# PIC.net
KiCad netlist of a schematic drawn in Altium Designer
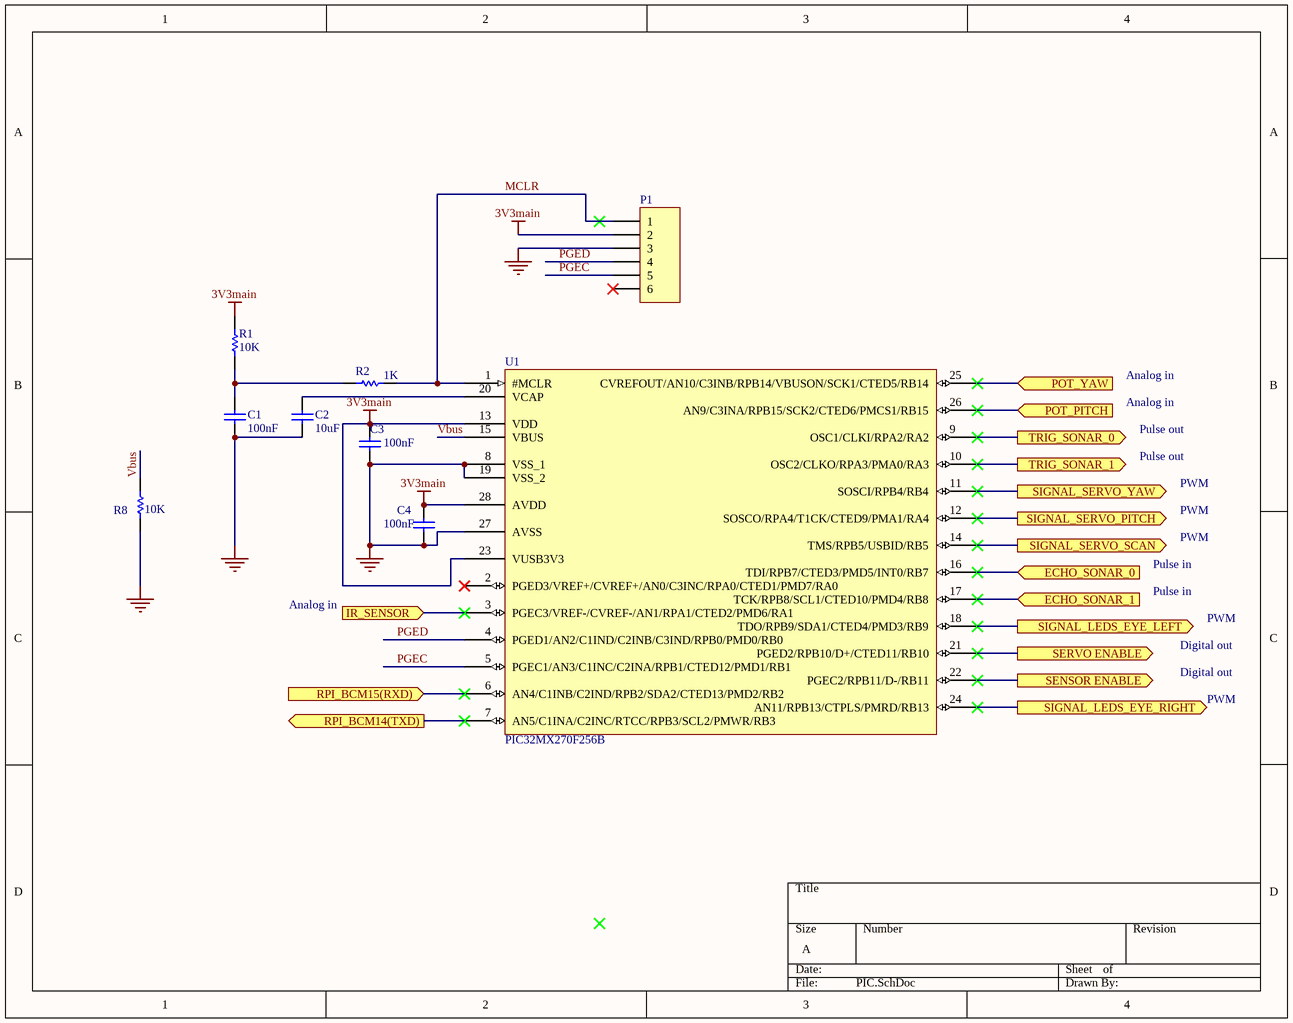
[diagram p0: PIC.SchDoc]

(export (version "E")
  (design (tool "Eeschema 10.0.6"))
  (components
    (comp (ref "C1")
      (value "100nF")
      (footprint "1608 / 0603")
      (description "Capacitor")
      (fields (field (name "PUBLISHER") "Altium Limited"))
      (libsource (lib "Miscellaneous Devices") (part "Cap"))
    )
    (comp (ref "C2")
      (value "10uF")
      (footprint "1608 / 0603")
      (description "Capacitor")
      (fields (field (name "PUBLISHER") "Altium Limited"))
      (libsource (lib "Miscellaneous Devices") (part "Cap"))
    )
    (comp (ref "C3")
      (value "100nF")
      (footprint "1608 / 0603")
      (description "Capacitor")
      (fields (field (name "PUBLISHER") "Altium Limited"))
      (libsource (lib "Miscellaneous Devices") (part "Cap"))
    )
    (comp (ref "C4")
      (value "100nF")
      (footprint "1608 / 0603")
      (description "Capacitor")
      (fields (field (name "PUBLISHER") "Altium Limited"))
      (libsource (lib "Miscellaneous Devices") (part "Cap"))
    )
    (comp (ref "P1")
      (value "RJ11 Debug")
      (footprint "MarvinPcbLib2:RJ11")
      (description "RJ11 Connector")
      (fields (field (name "PUBLISHER") "Altium Limited"))
      (libsource (lib "Miscellaneous Connectors") (part "Header 6"))
    )
    (comp (ref "R1")
      (value "10K")
      (footprint "1608 / 0603")
      (description "Resistor")
      (fields (field (name "PUBLISHER") "Altium Limited"))
      (libsource (lib "Miscellaneous Devices") (part "Res1"))
    )
    (comp (ref "R2")
      (value "1K")
      (footprint "1608 / 0603")
      (description "Resistor")
      (fields (field (name "PUBLISHER") "Altium Limited"))
      (libsource (lib "Miscellaneous Devices") (part "Res1"))
    )
    (comp (ref "R8")
      (value "10K")
      (footprint "1608 / 0603")
      (description "Resistor")
      (fields (field (name "PUBLISHER") "Altium Limited"))
      (libsource (lib "Miscellaneous Devices") (part "Res1"))
    )
    (comp (ref "U1")
      (value "PIC32MX270F256B")
      (footprint "MarvinPcbLib2:SOIC28")
      (libsource (lib "POC_Marvin") (part "PIC32MX270F256B"))
    )
  )
  (nets
    (net (code "1") (name "/ECHO_SONAR_0") (class "Default")
      (node (ref "U1") (pin "16") (pinfunction "TDI/RPB7/CTED3/PMD5/INT0/RB7_16") (pintype "bidirectional+no_connect"))
    )
    (net (code "2") (name "/ECHO_SONAR_1") (class "Default")
      (node (ref "U1") (pin "17") (pinfunction "TCK/RPB8/SCL1/CTED10/PMD4/RB8_17") (pintype "bidirectional+no_connect"))
    )
    (net (code "3") (name "/IR_SENSOR") (class "Default")
      (node (ref "U1") (pin "3") (pinfunction "PGEC3/VREF-/CVREF-/AN1/RPA1/CTED2/PMD6/RA1_3") (pintype "bidirectional+no_connect"))
    )
    (net (code "4") (name "/MCLR") (class "Default")
      (node (ref "P1") (pin "1") (pinfunction "1_1") (pintype "passive"))
      (node (ref "R2") (pin "2") (pinfunction "2_2") (pintype "passive"))
      (node (ref "U1") (pin "1") (pinfunction "#MCLR_1") (pintype "input"))
    )
    (net (code "5") (name "/PGEC") (class "Default")
      (node (ref "P1") (pin "5") (pinfunction "5_5") (pintype "passive"))
      (node (ref "U1") (pin "5") (pinfunction "PGEC1/AN3/C1INC/C2INA/RPB1/CTED12/PMD1/RB1_5") (pintype "bidirectional"))
    )
    (net (code "6") (name "/PGED") (class "Default")
      (node (ref "P1") (pin "4") (pinfunction "4_4") (pintype "passive"))
      (node (ref "U1") (pin "4") (pinfunction "PGED1/AN2/C1IND/C2INB/C3IND/RPB0/PMD0/RB0_4") (pintype "bidirectional"))
    )
    (net (code "7") (name "/POT_PITCH") (class "Default")
      (node (ref "U1") (pin "26") (pinfunction "AN9/C3INA/RPB15/SCK2/CTED6/PMCS1/RB15_26") (pintype "bidirectional+no_connect"))
    )
    (net (code "8") (name "/POT_YAW") (class "Default")
      (node (ref "U1") (pin "25") (pinfunction "CVREFOUT/AN10/C3INB/RPB14/VBUSON/SCK1/CTED5/RB14_25") (pintype "bidirectional+no_connect"))
    )
    (net (code "9") (name "/RPI_BCM14(TXD)") (class "Default")
      (node (ref "U1") (pin "7") (pinfunction "AN5/C1INA/C2INC/RTCC/RPB3/SCL2/PMWR/RB3_7") (pintype "bidirectional+no_connect"))
    )
    (net (code "10") (name "/RPI_BCM15(RXD)") (class "Default")
      (node (ref "U1") (pin "6") (pinfunction "AN4/C1INB/C2IND/RPB2/SDA2/CTED13/PMD2/RB2_6") (pintype "bidirectional+no_connect"))
    )
    (net (code "11") (name "/SENSOR ENABLE") (class "Default")
      (node (ref "U1") (pin "22") (pinfunction "PGEC2/RPB11/D-/RB11_22") (pintype "bidirectional+no_connect"))
    )
    (net (code "12") (name "/SERVO ENABLE") (class "Default")
      (node (ref "U1") (pin "21") (pinfunction "PGED2/RPB10/D+/CTED11/RB10_21") (pintype "bidirectional+no_connect"))
    )
    (net (code "13") (name "/SIGNAL_LEDS_EYE_LEFT") (class "Default")
      (node (ref "U1") (pin "18") (pinfunction "TDO/RPB9/SDA1/CTED4/PMD3/RB9_18") (pintype "bidirectional+no_connect"))
    )
    (net (code "14") (name "/SIGNAL_LEDS_EYE_RIGHT") (class "Default")
      (node (ref "U1") (pin "24") (pinfunction "AN11/RPB13/CTPLS/PMRD/RB13_24") (pintype "bidirectional+no_connect"))
    )
    (net (code "15") (name "/SIGNAL_SERVO_PITCH") (class "Default")
      (node (ref "U1") (pin "12") (pinfunction "SOSCO/RPA4/T1CK/CTED9/PMA1/RA4_12") (pintype "bidirectional+no_connect"))
    )
    (net (code "16") (name "/SIGNAL_SERVO_SCAN") (class "Default")
      (node (ref "U1") (pin "14") (pinfunction "TMS/RPB5/USBID/RB5_14") (pintype "bidirectional+no_connect"))
    )
    (net (code "17") (name "/SIGNAL_SERVO_YAW") (class "Default")
      (node (ref "U1") (pin "11") (pinfunction "SOSCI/RPB4/RB4_11") (pintype "bidirectional+no_connect"))
    )
    (net (code "18") (name "/TRIG_SONAR_0") (class "Default")
      (node (ref "U1") (pin "9") (pinfunction "OSC1/CLKI/RPA2/RA2_9") (pintype "bidirectional+no_connect"))
    )
    (net (code "19") (name "/TRIG_SONAR_1") (class "Default")
      (node (ref "U1") (pin "10") (pinfunction "OSC2/CLKO/RPA3/PMA0/RA3_10") (pintype "bidirectional+no_connect"))
    )
    (net (code "20") (name "/Vbus") (class "Default")
      (node (ref "R8") (pin "2") (pinfunction "2_2") (pintype "passive"))
      (node (ref "U1") (pin "15") (pinfunction "VBUS_15") (pintype "power_in"))
    )
    (net (code "21") (name "3V3main") (class "Default")
      (node (ref "C3") (pin "2") (pinfunction "2_2") (pintype "passive"))
      (node (ref "C4") (pin "2") (pinfunction "2_2") (pintype "passive"))
      (node (ref "P1") (pin "2") (pinfunction "2_2") (pintype "passive"))
      (node (ref "R1") (pin "2") (pinfunction "2_2") (pintype "passive"))
      (node (ref "U1") (pin "13") (pinfunction "VDD_13") (pintype "power_in"))
      (node (ref "U1") (pin "23") (pinfunction "VUSB3V3_23") (pintype "power_in"))
      (node (ref "U1") (pin "28") (pinfunction "AVDD_28") (pintype "power_in"))
    )
    (net (code "22") (name "GND") (class "Default")
      (node (ref "C1") (pin "1") (pinfunction "1_1") (pintype "passive"))
      (node (ref "C2") (pin "1") (pinfunction "1_1") (pintype "passive"))
      (node (ref "C3") (pin "1") (pinfunction "1_1") (pintype "passive"))
      (node (ref "C4") (pin "1") (pinfunction "1_1") (pintype "passive"))
      (node (ref "P1") (pin "3") (pinfunction "3_3") (pintype "passive"))
      (node (ref "R8") (pin "1") (pinfunction "1_1") (pintype "passive"))
      (node (ref "U1") (pin "19") (pinfunction "VSS_2_19") (pintype "power_in"))
      (node (ref "U1") (pin "27") (pinfunction "AVSS_27") (pintype "power_in"))
      (node (ref "U1") (pin "8") (pinfunction "VSS_1_8") (pintype "power_in"))
    )
    (net (code "23") (name "Net-(C1-Pad2)") (class "Default")
      (node (ref "C1") (pin "2") (pinfunction "2_2") (pintype "passive"))
      (node (ref "R1") (pin "1") (pinfunction "1_1") (pintype "passive"))
      (node (ref "R2") (pin "1") (pinfunction "1_1") (pintype "passive"))
    )
    (net (code "24") (name "Net-(U1-VCAP)") (class "Default")
      (node (ref "C2") (pin "2") (pinfunction "2_2") (pintype "passive"))
      (node (ref "U1") (pin "20") (pinfunction "VCAP_20") (pintype "power_in"))
    )
    (net (code "25") (name "unconnected-(P1-Pad6)") (class "Default")
      (node (ref "P1") (pin "6") (pinfunction "6_6") (pintype "passive+no_connect"))
    )
    (net (code "26") (name "unconnected-(U1-PGED3{slash}VREF+{slash}CVREF+{slash}AN0{slash}C3INC{slash}RPA0{slash}CTED1{slash}PMD7{slash}RA0-Pad2)") (class "Default")
      (node (ref "U1") (pin "2") (pinfunction "PGED3/VREF+/CVREF+/AN0/C3INC/RPA0/CTED1/PMD7/RA0_2") (pintype "bidirectional+no_connect"))
    )
  )
)
